# adc.net
KiCad netlist of a schematic drawn in Altium Designer
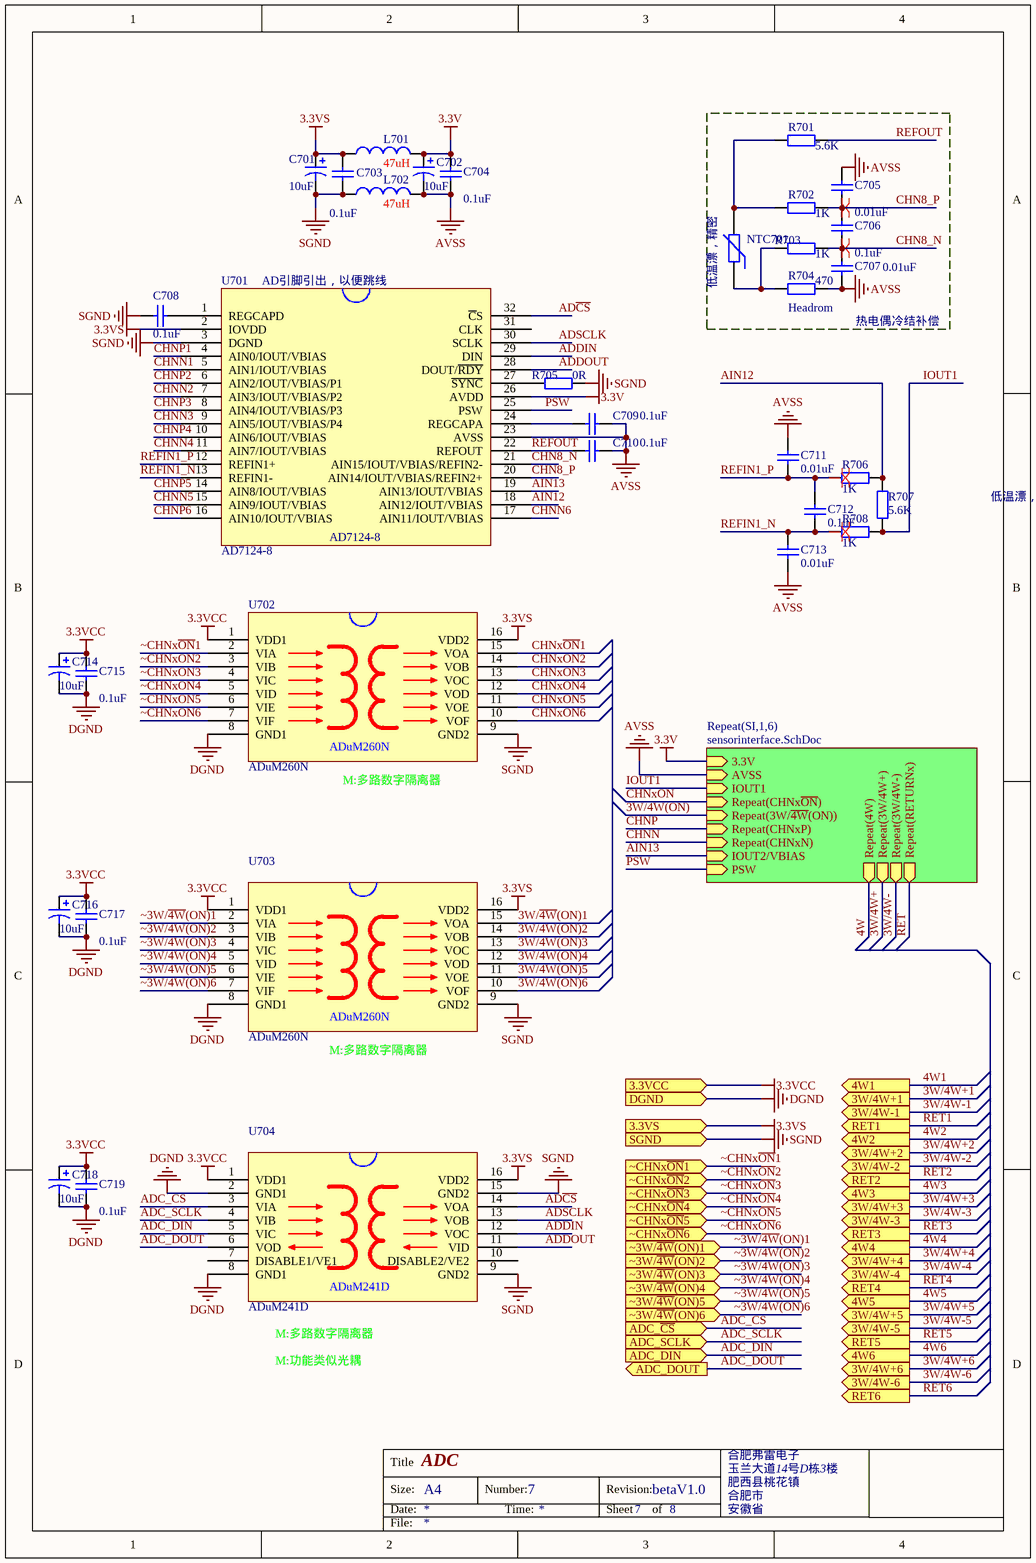
[diagram p0: adc.SchDoc]

(export (version "E")
  (design (tool "Eeschema 10.0.6"))
  (components
    (comp (ref "C701")
      (value "10uF")
      (footprint "mmyLibrary:CB")
      (description "Polarized Capacitor (Radial)")
      (fields (field (name "Comment") "T494B106M006AHAUTO") (field (name "PUBLISHER") "Altium Limited"))
      (libsource (lib "Miscellaneous Devices") (part "Cap Pol1"))
    )
    (comp (ref "C702")
      (value "10uF")
      (footprint "mmyLibrary:CB")
      (description "Polarized Capacitor (Radial)")
      (fields (field (name "Comment") "T494B106M006AHAUTO") (field (name "PUBLISHER") "Altium Limited"))
      (libsource (lib "Miscellaneous Devices") (part "Cap Pol1"))
    )
    (comp (ref "C703")
      (value "0.1uF")
      (footprint "0603C")
      (description "Capacitor")
      (fields (field (name "Comment") "CC0805MRX7R9BB104") (field (name "PUBLISHER") "Altium Limited"))
      (libsource (lib "Miscellaneous Devices") (part "Cap"))
    )
    (comp (ref "C704")
      (value "0.1uF")
      (footprint "0603C")
      (description "Capacitor")
      (fields (field (name "Comment") "CC0805MRX7R9BB104") (field (name "PUBLISHER") "Altium Limited"))
      (libsource (lib "Miscellaneous Devices") (part "Cap"))
    )
    (comp (ref "C705")
      (value "0.01uF")
      (footprint "0603C")
      (description "Capacitor")
      (fields (field (name "Comment") "CC0805MRX7R9BB103") (field (name "PUBLISHER") "Altium Limited"))
      (libsource (lib "Miscellaneous Devices") (part "Cap"))
    )
    (comp (ref "C706")
      (value "0.1uF")
      (footprint "0603C")
      (description "Capacitor")
      (fields (field (name "Comment") "CC0805MRX7R9BB104") (field (name "PUBLISHER") "Altium Limited"))
      (libsource (lib "Miscellaneous Devices") (part "Cap"))
    )
    (comp (ref "C707")
      (value "0.01uF")
      (footprint "0603C")
      (description "Capacitor")
      (fields (field (name "Comment") "CC0805MRX7R9BB103") (field (name "PUBLISHER") "Altium Limited"))
      (libsource (lib "Miscellaneous Devices") (part "Cap"))
    )
    (comp (ref "C708")
      (value "0.1uF")
      (footprint "0603C")
      (description "Capacitor")
      (fields (field (name "Comment") "CC0805MRX7R9BB104") (field (name "PUBLISHER") "Altium Limited"))
      (libsource (lib "Miscellaneous Devices") (part "Cap"))
    )
    (comp (ref "C709")
      (value "0.1uF")
      (footprint "0603C")
      (description "Capacitor")
      (fields (field (name "Comment") "CC0805MRX7R9BB104") (field (name "PUBLISHER") "Altium Limited"))
      (libsource (lib "Miscellaneous Devices") (part "Cap"))
    )
    (comp (ref "C710")
      (value "0.1uF")
      (footprint "0603C")
      (description "Capacitor")
      (fields (field (name "Comment") "CC0805MRX7R9BB104") (field (name "PUBLISHER") "Altium Limited"))
      (libsource (lib "Miscellaneous Devices") (part "Cap"))
    )
    (comp (ref "C711")
      (value "0.01uF")
      (footprint "0603C")
      (description "Capacitor")
      (fields (field (name "Comment") "CC0805MRX7R9BB103") (field (name "PUBLISHER") "Altium Limited"))
      (libsource (lib "Miscellaneous Devices") (part "Cap"))
    )
    (comp (ref "C712")
      (value "0.1uF")
      (footprint "0603C")
      (description "Capacitor")
      (fields (field (name "Comment") "CC0805MRX7R9BB104") (field (name "PUBLISHER") "Altium Limited"))
      (libsource (lib "Miscellaneous Devices") (part "Cap"))
    )
    (comp (ref "C713")
      (value "0.01uF")
      (footprint "0603C")
      (description "Capacitor")
      (fields (field (name "Comment") "CC0805MRX7R9BB103") (field (name "PUBLISHER") "Altium Limited"))
      (libsource (lib "Miscellaneous Devices") (part "Cap"))
    )
    (comp (ref "C714")
      (value "10uF")
      (footprint "mmyLibrary:CB")
      (description "Polarized Capacitor (Radial)")
      (fields (field (name "Comment") "T494B106M006AHAUTO") (field (name "PUBLISHER") "Altium Limited"))
      (libsource (lib "Miscellaneous Devices") (part "Cap Pol1"))
    )
    (comp (ref "C715")
      (value "0.1uF")
      (footprint "0603C")
      (description "Capacitor")
      (fields (field (name "Comment") "CC0805MRX7R9BB104") (field (name "PUBLISHER") "Altium Limited"))
      (libsource (lib "Miscellaneous Devices") (part "Cap"))
    )
    (comp (ref "C716")
      (value "10uF")
      (footprint "mmyLibrary:CB")
      (description "Polarized Capacitor (Radial)")
      (fields (field (name "Comment") "T494B106M006AHAUTO") (field (name "PUBLISHER") "Altium Limited"))
      (libsource (lib "Miscellaneous Devices") (part "Cap Pol1"))
    )
    (comp (ref "C717")
      (value "0.1uF")
      (footprint "0603C")
      (description "Capacitor")
      (fields (field (name "Comment") "CC0805MRX7R9BB104") (field (name "PUBLISHER") "Altium Limited"))
      (libsource (lib "Miscellaneous Devices") (part "Cap"))
    )
    (comp (ref "C718")
      (value "10uF")
      (footprint "mmyLibrary:CB")
      (description "Polarized Capacitor (Radial)")
      (fields (field (name "Comment") "T494B106M006AHAUTO") (field (name "PUBLISHER") "Altium Limited"))
      (libsource (lib "Miscellaneous Devices") (part "Cap Pol1"))
    )
    (comp (ref "C719")
      (value "0.1uF")
      (footprint "0603C")
      (description "Capacitor")
      (fields (field (name "Comment") "CC0805MRX7R9BB104") (field (name "PUBLISHER") "Altium Limited"))
      (libsource (lib "Miscellaneous Devices") (part "Cap"))
    )
    (comp (ref "L701")
      (value "47uH")
      (footprint "mmyLibrary:0805r")
      (fields (field (name "Comment") "VLS4012HBX-150M"))
      (libsource (lib "Miscellaneous Devices") (part "Inductor"))
    )
    (comp (ref "L702")
      (value "47uH")
      (footprint "mmyLibrary:0805r")
      (fields (field (name "Comment") "VLS4012HBX-150M"))
      (libsource (lib "Miscellaneous Devices") (part "Inductor"))
    )
    (comp (ref "NTC701")
      (value "NTCS0805E3103JHT")
      (footprint "mmyLibrary:0805r")
      (description "Varistor (Voltage-Sensitive Resistor)")
      (fields (field (name "PUBLISHER") "Altium Limited"))
      (libsource (lib "Miscellaneous Devices") (part "Res Varistor"))
    )
    (comp (ref "R701")
      (value "5.6K")
      (footprint "0603R")
      (description "Resistor")
      (fields (field (name "Comment") "RC0805JR-075600RL") (field (name "PUBLISHER") "Altium Limited"))
      (libsource (lib "") (part "Res2_2"))
    )
    (comp (ref "R702")
      (value "1K")
      (footprint "0603R")
      (description "Resistor")
      (fields (field (name "Comment") "RC0805JR-071KL") (field (name "PUBLISHER") "Altium Limited"))
      (libsource (lib "") (part "Res2_2"))
    )
    (comp (ref "R703")
      (value "1K")
      (footprint "0603R")
      (description "Resistor")
      (fields (field (name "Comment") "RC0805JR-071KL") (field (name "PUBLISHER") "Altium Limited"))
      (libsource (lib "") (part "Res2_2"))
    )
    (comp (ref "R704")
      (value "470")
      (footprint "0603R")
      (description "Resistor")
      (fields (field (name "Comment") "RC0805JR-07470RL") (field (name "PUBLISHER") "Altium Limited"))
      (libsource (lib "") (part "Res2_2"))
    )
    (comp (ref "R705")
      (value "0R")
      (footprint "0603R")
      (description "Resistor")
      (fields (field (name "Comment") "RC0805JR-000KL") (field (name "PUBLISHER") "Altium Limited"))
      (libsource (lib "") (part "Res2_1"))
    )
    (comp (ref "R706")
      (value "1K")
      (footprint "0603R")
      (description "Resistor")
      (fields (field (name "Comment") "RC0805JR-071KL") (field (name "PUBLISHER") "Altium Limited"))
      (libsource (lib "Miscellaneous Devices") (part "Res2"))
    )
    (comp (ref "R707")
      (value "5.6K")
      (footprint "0603R")
      (description "Resistor")
      (fields (field (name "Comment") "RC0805JR-075600RL") (field (name "PUBLISHER") "Altium Limited"))
      (libsource (lib "") (part "Res2_1"))
    )
    (comp (ref "R708")
      (value "1K")
      (footprint "0603R")
      (description "Resistor")
      (fields (field (name "Comment") "RC0805JR-071KL") (field (name "PUBLISHER") "Altium Limited"))
      (libsource (lib "Miscellaneous Devices") (part "Res2"))
    )
    (comp (ref "U701")
      (value "AD7124-8")
      (footprint "TI-RHB32-3150X3150TP_V")
      (libsource (lib "AD_Sch_Lib") (part "AD7124-8"))
    )
    (comp (ref "U702")
      (value "ADuM260N")
      (footprint "SOIC-16")
      (libsource (lib "Standard-V0.0") (part "ADuM260N"))
    )
    (comp (ref "U703")
      (value "ADuM260N")
      (footprint "SOIC-16")
      (libsource (lib "Standard-V0.0") (part "ADuM260N"))
    )
    (comp (ref "U704")
      (value "ADuM241D")
      (footprint "SOIC-16")
      (libsource (lib "Standard-V0.0") (part "ADuM241D"))
    )
  )
  (nets
    (net (code "16") (name "/3W{slash}~{4W}(ON)1") (class "Default")
      (node (ref "U703") (pin "15") (pinfunction "VOA_15") (pintype "passive"))
    )
    (net (code "17") (name "/3W{slash}~{4W}(ON)2") (class "Default")
      (node (ref "U703") (pin "14") (pinfunction "VOB_14") (pintype "passive"))
    )
    (net (code "18") (name "/3W{slash}~{4W}(ON)3") (class "Default")
      (node (ref "U703") (pin "13") (pinfunction "VOC_13") (pintype "passive"))
    )
    (net (code "19") (name "/3W{slash}~{4W}(ON)4") (class "Default")
      (node (ref "U703") (pin "12") (pinfunction "VOD_12") (pintype "passive"))
    )
    (net (code "20") (name "/3W{slash}~{4W}(ON)5") (class "Default")
      (node (ref "U703") (pin "11") (pinfunction "VOE_11") (pintype "passive"))
    )
    (net (code "21") (name "/3W{slash}~{4W}(ON)6") (class "Default")
      (node (ref "U703") (pin "10") (pinfunction "VOF_10") (pintype "passive"))
    )
    (net (code "29") (name "/ADC_DIN") (class "Default")
      (node (ref "U704") (pin "5") (pinfunction "VIC_5") (pintype "passive"))
    )
    (net (code "30") (name "/ADC_DOUT") (class "Default")
      (node (ref "U704") (pin "6") (pinfunction "VOD_6") (pintype "passive"))
    )
    (net (code "31") (name "/ADC_SCLK") (class "Default")
      (node (ref "U704") (pin "4") (pinfunction "VIB_4") (pintype "passive"))
    )
    (net (code "32") (name "/ADC_~{CS}") (class "Default")
      (node (ref "U704") (pin "3") (pinfunction "VIA_3") (pintype "passive"))
    )
    (net (code "33") (name "/ADDIN") (class "Default")
      (node (ref "U701") (pin "29") (pinfunction "DIN_29") (pintype "passive"))
      (node (ref "U704") (pin "12") (pinfunction "VOC_12") (pintype "passive"))
    )
    (net (code "34") (name "/ADDOUT") (class "Default")
      (node (ref "U701") (pin "28") (pinfunction "DOUT/~{RDY}_28") (pintype "passive"))
      (node (ref "U704") (pin "11") (pinfunction "VID_11") (pintype "passive"))
    )
    (net (code "35") (name "/ADSCLK") (class "Default")
      (node (ref "U701") (pin "30") (pinfunction "SCLK_30") (pintype "passive"))
      (node (ref "U704") (pin "13") (pinfunction "VOB_13") (pintype "passive"))
    )
    (net (code "36") (name "/AD~{CS}") (class "Default")
      (node (ref "U701") (pin "32") (pinfunction "~{C}S_32") (pintype "passive"))
      (node (ref "U704") (pin "14") (pinfunction "VOA_14") (pintype "passive"))
    )
    (net (code "37") (name "/AIN12") (class "Default")
      (node (ref "R706") (pin "2") (pinfunction "2_2") (pintype "passive"))
      (node (ref "R707") (pin "2") (pinfunction "2_2") (pintype "passive"))
      (node (ref "U701") (pin "18") (pinfunction "AIN12/IOUT/VBIAS_18") (pintype "passive"))
    )
    (net (code "38") (name "/AIN13") (class "Default")
      (node (ref "U701") (pin "19") (pinfunction "AIN13/IOUT/VBIAS_19") (pintype "passive"))
    )
    (net (code "39") (name "/CHN8_N") (class "Default")
      (node (ref "C706") (pin "2") (pinfunction "2_2") (pintype "passive"))
      (node (ref "C707") (pin "1") (pinfunction "1_1") (pintype "passive"))
      (node (ref "R703") (pin "1") (pinfunction "1_1") (pintype "passive"))
      (node (ref "U701") (pin "21") (pinfunction "AIN15/IOUT/VBIAS/REFIN2-_21") (pintype "passive"))
    )
    (net (code "40") (name "/CHN8_P") (class "Default")
      (node (ref "C705") (pin "1") (pinfunction "1_1") (pintype "passive"))
      (node (ref "C706") (pin "1") (pinfunction "1_1") (pintype "passive"))
      (node (ref "R702") (pin "1") (pinfunction "1_1") (pintype "passive"))
      (node (ref "U701") (pin "20") (pinfunction "AIN14/IOUT/VBIAS/REFIN2+_20") (pintype "passive"))
    )
    (net (code "42") (name "/CHNN1") (class "Default")
      (node (ref "U701") (pin "5") (pinfunction "AIN1/IOUT/VBIAS_5") (pintype "passive"))
    )
    (net (code "43") (name "/CHNN2") (class "Default")
      (node (ref "U701") (pin "7") (pinfunction "AIN3/IOUT/VBIAS/P2_7") (pintype "passive"))
    )
    (net (code "44") (name "/CHNN3") (class "Default")
      (node (ref "U701") (pin "9") (pinfunction "AIN5/IOUT/VBIAS/P4_9") (pintype "passive"))
    )
    (net (code "45") (name "/CHNN4") (class "Default")
      (node (ref "U701") (pin "11") (pinfunction "AIN7/IOUT/VBIAS_11") (pintype "passive"))
    )
    (net (code "46") (name "/CHNN5") (class "Default")
      (node (ref "U701") (pin "15") (pinfunction "AIN9/IOUT/VBIAS_15") (pintype "passive"))
    )
    (net (code "47") (name "/CHNN6") (class "Default")
      (node (ref "U701") (pin "17") (pinfunction "AIN11/IOUT/VBIAS_17") (pintype "passive"))
    )
    (net (code "49") (name "/CHNP1") (class "Default")
      (node (ref "U701") (pin "4") (pinfunction "AIN0/IOUT/VBIAS_4") (pintype "passive"))
    )
    (net (code "50") (name "/CHNP2") (class "Default")
      (node (ref "U701") (pin "6") (pinfunction "AIN2/IOUT/VBIAS/P1_6") (pintype "passive"))
    )
    (net (code "51") (name "/CHNP3") (class "Default")
      (node (ref "U701") (pin "8") (pinfunction "AIN4/IOUT/VBIAS/P3_8") (pintype "passive"))
    )
    (net (code "52") (name "/CHNP4") (class "Default")
      (node (ref "U701") (pin "10") (pinfunction "AIN6/IOUT/VBIAS_10") (pintype "passive"))
    )
    (net (code "53") (name "/CHNP5") (class "Default")
      (node (ref "U701") (pin "14") (pinfunction "AIN8/IOUT/VBIAS_14") (pintype "passive"))
    )
    (net (code "54") (name "/CHNP6") (class "Default")
      (node (ref "U701") (pin "16") (pinfunction "AIN10/IOUT/VBIAS_16") (pintype "passive"))
    )
    (net (code "56") (name "/CHNx~{ON}1") (class "Default")
      (node (ref "U702") (pin "15") (pinfunction "VOA_15") (pintype "passive"))
    )
    (net (code "57") (name "/CHNx~{ON}2") (class "Default")
      (node (ref "U702") (pin "14") (pinfunction "VOB_14") (pintype "passive"))
    )
    (net (code "58") (name "/CHNx~{ON}3") (class "Default")
      (node (ref "U702") (pin "13") (pinfunction "VOC_13") (pintype "passive"))
    )
    (net (code "59") (name "/CHNx~{ON}4") (class "Default")
      (node (ref "U702") (pin "12") (pinfunction "VOD_12") (pintype "passive"))
    )
    (net (code "60") (name "/CHNx~{ON}5") (class "Default")
      (node (ref "U702") (pin "11") (pinfunction "VOE_11") (pintype "passive"))
    )
    (net (code "61") (name "/CHNx~{ON}6") (class "Default")
      (node (ref "U702") (pin "10") (pinfunction "VOF_10") (pintype "passive"))
    )
    (net (code "62") (name "/IOUT1") (class "Default")
      (node (ref "R707") (pin "1") (pinfunction "1_1") (pintype "passive"))
      (node (ref "R708") (pin "2") (pinfunction "2_2") (pintype "passive"))
    )
    (net (code "63") (name "/PSW") (class "Default")
      (node (ref "U701") (pin "25") (pinfunction "PSW_25") (pintype "passive"))
    )
    (net (code "64") (name "/REFIN1_N") (class "Default")
      (node (ref "C712") (pin "2") (pinfunction "2_2") (pintype "passive"))
      (node (ref "C713") (pin "1") (pinfunction "1_1") (pintype "passive"))
      (node (ref "R708") (pin "1") (pinfunction "1_1") (pintype "passive"))
      (node (ref "U701") (pin "13") (pinfunction "REFIN1-_13") (pintype "passive"))
    )
    (net (code "65") (name "/REFIN1_P") (class "Default")
      (node (ref "C711") (pin "1") (pinfunction "1_1") (pintype "passive"))
      (node (ref "C712") (pin "1") (pinfunction "1_1") (pintype "passive"))
      (node (ref "R706") (pin "1") (pinfunction "1_1") (pintype "passive"))
      (node (ref "U701") (pin "12") (pinfunction "REFIN1+_12") (pintype "passive"))
    )
    (net (code "66") (name "/REFOUT") (class "Default")
      (node (ref "C710") (pin "2") (pinfunction "2_2") (pintype "passive"))
      (node (ref "R701") (pin "1") (pinfunction "1_1") (pintype "passive"))
      (node (ref "U701") (pin "22") (pinfunction "REFOUT_22") (pintype "passive"))
    )
    (net (code "74") (name "/~3W{slash}~{4W}(ON)1") (class "Default")
      (node (ref "U703") (pin "2") (pinfunction "VIA_2") (pintype "passive"))
    )
    (net (code "75") (name "/~3W{slash}~{4W}(ON)2") (class "Default")
      (node (ref "U703") (pin "3") (pinfunction "VIB_3") (pintype "passive"))
    )
    (net (code "76") (name "/~3W{slash}~{4W}(ON)3") (class "Default")
      (node (ref "U703") (pin "4") (pinfunction "VIC_4") (pintype "passive"))
    )
    (net (code "77") (name "/~3W{slash}~{4W}(ON)4") (class "Default")
      (node (ref "U703") (pin "5") (pinfunction "VID_5") (pintype "passive"))
    )
    (net (code "78") (name "/~3W{slash}~{4W}(ON)5") (class "Default")
      (node (ref "U703") (pin "6") (pinfunction "VIE_6") (pintype "passive"))
    )
    (net (code "79") (name "/~3W{slash}~{4W}(ON)6") (class "Default")
      (node (ref "U703") (pin "7") (pinfunction "VIF_7") (pintype "passive"))
    )
    (net (code "80") (name "/~CHNx~{ON}1") (class "Default")
      (node (ref "U702") (pin "2") (pinfunction "VIA_2") (pintype "passive"))
    )
    (net (code "81") (name "/~CHNx~{ON}2") (class "Default")
      (node (ref "U702") (pin "3") (pinfunction "VIB_3") (pintype "passive"))
    )
    (net (code "82") (name "/~CHNx~{ON}3") (class "Default")
      (node (ref "U702") (pin "4") (pinfunction "VIC_4") (pintype "passive"))
    )
    (net (code "83") (name "/~CHNx~{ON}4") (class "Default")
      (node (ref "U702") (pin "5") (pinfunction "VID_5") (pintype "passive"))
    )
    (net (code "84") (name "/~CHNx~{ON}5") (class "Default")
      (node (ref "U702") (pin "6") (pinfunction "VIE_6") (pintype "passive"))
    )
    (net (code "85") (name "/~CHNx~{ON}6") (class "Default")
      (node (ref "U702") (pin "7") (pinfunction "VIF_7") (pintype "passive"))
    )
    (net (code "86") (name "3.3V") (class "Default")
      (node (ref "C702") (pin "1") (pinfunction "1_1") (pintype "passive"))
      (node (ref "C704") (pin "1") (pinfunction "1_1") (pintype "passive"))
      (node (ref "L701") (pin "2") (pinfunction "2_2") (pintype "passive"))
      (node (ref "U701") (pin "26") (pinfunction "AVDD_26") (pintype "passive"))
    )
    (net (code "87") (name "3.3VCC") (class "Default")
      (node (ref "C714") (pin "1") (pinfunction "1_1") (pintype "passive"))
      (node (ref "C715") (pin "1") (pinfunction "1_1") (pintype "passive"))
      (node (ref "C716") (pin "1") (pinfunction "1_1") (pintype "passive"))
      (node (ref "C717") (pin "1") (pinfunction "1_1") (pintype "passive"))
      (node (ref "C718") (pin "1") (pinfunction "1_1") (pintype "passive"))
      (node (ref "C719") (pin "1") (pinfunction "1_1") (pintype "passive"))
      (node (ref "U702") (pin "1") (pinfunction "VDD1_1") (pintype "passive"))
      (node (ref "U703") (pin "1") (pinfunction "VDD1_1") (pintype "passive"))
      (node (ref "U704") (pin "1") (pinfunction "VDD1_1") (pintype "passive"))
    )
    (net (code "88") (name "3.3VS") (class "Default")
      (node (ref "C701") (pin "1") (pinfunction "1_1") (pintype "passive"))
      (node (ref "C703") (pin "1") (pinfunction "1_1") (pintype "passive"))
      (node (ref "L701") (pin "1") (pinfunction "1_1") (pintype "passive"))
      (node (ref "U701") (pin "2") (pinfunction "IOVDD_2") (pintype "passive"))
      (node (ref "U702") (pin "16") (pinfunction "VDD2_16") (pintype "passive"))
      (node (ref "U703") (pin "16") (pinfunction "VDD2_16") (pintype "passive"))
      (node (ref "U704") (pin "16") (pinfunction "VDD2_16") (pintype "passive"))
    )
    (net (code "89") (name "AVSS") (class "Default")
      (node (ref "C702") (pin "2") (pinfunction "2_2") (pintype "passive"))
      (node (ref "C704") (pin "2") (pinfunction "2_2") (pintype "passive"))
      (node (ref "C705") (pin "2") (pinfunction "2_2") (pintype "passive"))
      (node (ref "C707") (pin "2") (pinfunction "2_2") (pintype "passive"))
      (node (ref "C709") (pin "1") (pinfunction "1_1") (pintype "passive"))
      (node (ref "C710") (pin "1") (pinfunction "1_1") (pintype "passive"))
      (node (ref "C711") (pin "2") (pinfunction "2_2") (pintype "passive"))
      (node (ref "C713") (pin "2") (pinfunction "2_2") (pintype "passive"))
      (node (ref "L702") (pin "2") (pinfunction "2_2") (pintype "passive"))
      (node (ref "R704") (pin "1") (pinfunction "1_1") (pintype "passive"))
      (node (ref "U701") (pin "23") (pinfunction "AVSS_23") (pintype "passive"))
    )
    (net (code "90") (name "DGND") (class "Default")
      (node (ref "C714") (pin "2") (pinfunction "2_2") (pintype "passive"))
      (node (ref "C715") (pin "2") (pinfunction "2_2") (pintype "passive"))
      (node (ref "C716") (pin "2") (pinfunction "2_2") (pintype "passive"))
      (node (ref "C717") (pin "2") (pinfunction "2_2") (pintype "passive"))
      (node (ref "C718") (pin "2") (pinfunction "2_2") (pintype "passive"))
      (node (ref "C719") (pin "2") (pinfunction "2_2") (pintype "passive"))
      (node (ref "U702") (pin "8") (pinfunction "GND1_8") (pintype "passive"))
      (node (ref "U703") (pin "8") (pinfunction "GND1_8") (pintype "passive"))
      (node (ref "U704") (pin "2") (pinfunction "GND1_2") (pintype "passive"))
      (node (ref "U704") (pin "8") (pinfunction "GND1_8") (pintype "passive"))
    )
    (net (code "91") (name "Net-(NTC701-Pad1)") (class "Default")
      (node (ref "NTC701") (pin "1") (pinfunction "1_1") (pintype "passive"))
      (node (ref "R703") (pin "2") (pinfunction "2_2") (pintype "passive"))
      (node (ref "R704") (pin "2") (pinfunction "2_2") (pintype "passive"))
    )
    (net (code "92") (name "Net-(NTC701-Pad2)") (class "Default")
      (node (ref "NTC701") (pin "2") (pinfunction "2_2") (pintype "passive"))
      (node (ref "R701") (pin "2") (pinfunction "2_2") (pintype "passive"))
      (node (ref "R702") (pin "2") (pinfunction "2_2") (pintype "passive"))
    )
    (net (code "93") (name "Net-(U701-REGCAPA)") (class "Default")
      (node (ref "C709") (pin "2") (pinfunction "2_2") (pintype "passive"))
      (node (ref "U701") (pin "24") (pinfunction "REGCAPA_24") (pintype "passive"))
    )
    (net (code "94") (name "Net-(U701-REGCAPD)") (class "Default")
      (node (ref "C708") (pin "2") (pinfunction "2_2") (pintype "passive"))
      (node (ref "U701") (pin "1") (pinfunction "REGCAPD_1") (pintype "passive"))
    )
    (net (code "95") (name "Net-(U701-~{SYNC})") (class "Default")
      (node (ref "R705") (pin "1") (pinfunction "1_1") (pintype "passive"))
      (node (ref "U701") (pin "27") (pinfunction "~{SYNC}_27") (pintype "passive"))
    )
    (net (code "96") (name "SGND") (class "Default")
      (node (ref "C701") (pin "2") (pinfunction "2_2") (pintype "passive"))
      (node (ref "C703") (pin "2") (pinfunction "2_2") (pintype "passive"))
      (node (ref "C708") (pin "1") (pinfunction "1_1") (pintype "passive"))
      (node (ref "L702") (pin "1") (pinfunction "1_1") (pintype "passive"))
      (node (ref "R705") (pin "2") (pinfunction "2_2") (pintype "passive"))
      (node (ref "U701") (pin "3") (pinfunction "DGND_3") (pintype "passive"))
      (node (ref "U702") (pin "9") (pinfunction "GND2_9") (pintype "passive"))
      (node (ref "U703") (pin "9") (pinfunction "GND2_9") (pintype "passive"))
      (node (ref "U704") (pin "15") (pinfunction "GND2_15") (pintype "passive"))
      (node (ref "U704") (pin "9") (pinfunction "GND2_9") (pintype "passive"))
    )
    (net (code "97") (name "unconnected-(U701-CLK-Pad31)") (class "Default")
      (node (ref "U701") (pin "31") (pinfunction "CLK_31") (pintype "passive"))
    )
    (net (code "98") (name "unconnected-(U704-DISABLE1{slash}VE1-Pad7)") (class "Default")
      (node (ref "U704") (pin "7") (pinfunction "DISABLE1/VE1_7") (pintype "passive"))
    )
    (net (code "99") (name "unconnected-(U704-DISABLE2{slash}VE2-Pad10)") (class "Default")
      (node (ref "U704") (pin "10") (pinfunction "DISABLE2/VE2_10") (pintype "passive"))
    )
  )
)
